# LTM8074.net
KiCad netlist of a schematic drawn in Altium Designer
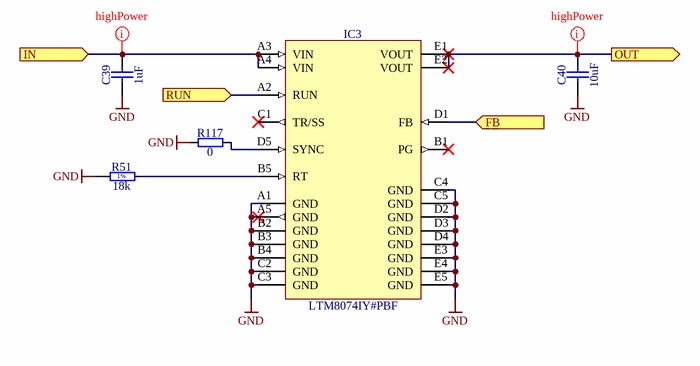
[diagram p0: LTM8074.SchDoc]

(export (version "E")
  (design (tool "Eeschema 10.0.6"))
  (components
    (comp (ref "C39")
      (value "1uF")
      (footprint "CAPC2012X110N")
      (description "Non-polarised capacitor")
      (fields
        (field (name "PART NUMBER") "CC0805_1UF_50V_10%_X7R")
        (field (name "VOLTAGE") "50V")
        (field (name "AUTHOR") "CERN DEM JLC")
      )
      (libsource (lib "Capacitors") (part "Capacitor - non polarized"))
    )
    (comp (ref "C40")
      (value "10uF")
      (footprint "CAPC2012X95N")
      (description "Non-polarised capacitor")
      (fields
        (field (name "PART NUMBER") "CC0805_10UF_25V_10%_X5R")
        (field (name "VOLTAGE") "25V")
        (field (name "AUTHOR") "CERN DEM JLC")
      )
      (libsource (lib "Capacitors") (part "Capacitor - non polarized"))
    )
    (comp (ref "IC3")
      (value "LTM8074IY#PBF")
      (footprint "BGA25C65P5X5_400X400X198")
      (description "40VIN, 1.2A Silent Switcher µModule Regulator")
      (fields (field (name "MANUFACTURER") "LINEAR TECHNOLOGY") (field (name "AUTHOR") "CERN DEM JLC"))
      (libsource (lib "ICs And Semiconductors") (part "LTM8074"))
    )
    (comp (ref "R51")
      (value "18k")
      (footprint "RESC1608X55N")
      (description "Resistor - 1%")
      (fields
        (field (name "PART NUMBER") "R0603_18K_1%_0.1W_100PPM")
        (field (name "POWER") "0.1W")
        (field (name "AUTHOR") "CERN DEM JLC")
      )
      (libsource (lib "Resistors") (part "Resistor - 1%"))
    )
    (comp (ref "R117")
      (value "0")
      (footprint "RESC1608X55N")
      (description "Resistor")
      (fields
        (field (name "PART NUMBER") "R0603_0R_JUMPER")
        (field (name "MANUFACTURER") "GENERIC")
        (field (name "AUTHOR") "CERN DEM JLC")
      )
      (libsource (lib "Resistors") (part "Resistor"))
    )
  )
  (nets
    (net (code "1") (name "/FB") (class "Default")
      (node (ref "IC3") (pin "D1") (pinfunction "FB_D1") (pintype "input"))
    )
    (net (code "2") (name "/IN") (class "Default")
      (node (ref "C39") (pin "2") (pinfunction "2_2") (pintype "passive"))
      (node (ref "IC3") (pin "A3") (pinfunction "VIN_A3") (pintype "input"))
      (node (ref "IC3") (pin "A4") (pinfunction "VIN_A4") (pintype "input"))
    )
    (net (code "3") (name "/OUT") (class "Default")
      (node (ref "C40") (pin "2") (pinfunction "2_2") (pintype "passive"))
      (node (ref "IC3") (pin "E1") (pinfunction "VOUT_E1") (pintype "power_in"))
      (node (ref "IC3") (pin "E2") (pinfunction "VOUT_E2") (pintype "power_in"))
    )
    (net (code "4") (name "/RUN") (class "Default")
      (node (ref "IC3") (pin "A2") (pinfunction "RUN_A2") (pintype "input"))
    )
    (net (code "5") (name "GND") (class "Default")
      (node (ref "C39") (pin "1") (pinfunction "1_1") (pintype "passive"))
      (node (ref "C40") (pin "1") (pinfunction "1_1") (pintype "passive"))
      (node (ref "IC3") (pin "A1") (pinfunction "GND_A1") (pintype "power_in"))
      (node (ref "IC3") (pin "A5") (pinfunction "GND_A5") (pintype "output"))
      (node (ref "IC3") (pin "B2") (pinfunction "GND_B2") (pintype "power_in"))
      (node (ref "IC3") (pin "B3") (pinfunction "GND_B3") (pintype "power_in"))
      (node (ref "IC3") (pin "B4") (pinfunction "GND_B4") (pintype "power_in"))
      (node (ref "IC3") (pin "C2") (pinfunction "GND_C2") (pintype "power_in"))
      (node (ref "IC3") (pin "C3") (pinfunction "GND_C3") (pintype "power_in"))
      (node (ref "IC3") (pin "C4") (pinfunction "GND_C4") (pintype "power_in"))
      (node (ref "IC3") (pin "C5") (pinfunction "GND_C5") (pintype "power_in"))
      (node (ref "IC3") (pin "D2") (pinfunction "GND_D2") (pintype "power_in"))
      (node (ref "IC3") (pin "D3") (pinfunction "GND_D3") (pintype "power_in"))
      (node (ref "IC3") (pin "D4") (pinfunction "GND_D4") (pintype "power_in"))
      (node (ref "IC3") (pin "E3") (pinfunction "GND_E3") (pintype "power_in"))
      (node (ref "IC3") (pin "E4") (pinfunction "GND_E4") (pintype "power_in"))
      (node (ref "IC3") (pin "E5") (pinfunction "GND_E5") (pintype "power_in"))
      (node (ref "R117") (pin "1") (pinfunction "1_1") (pintype "passive"))
      (node (ref "R51") (pin "1") (pinfunction "1_1") (pintype "passive"))
    )
    (net (code "6") (name "Net-(IC3-RT)") (class "Default")
      (node (ref "IC3") (pin "B5") (pinfunction "RT_B5") (pintype "input"))
      (node (ref "R51") (pin "2") (pinfunction "2_2") (pintype "passive"))
    )
    (net (code "7") (name "Net-(IC3-SYNC)") (class "Default")
      (node (ref "IC3") (pin "D5") (pinfunction "SYNC_D5") (pintype "input"))
      (node (ref "R117") (pin "2") (pinfunction "2_2") (pintype "passive"))
    )
    (net (code "8") (name "unconnected-(IC3-PG-PadB1)") (class "Default")
      (node (ref "IC3") (pin "B1") (pinfunction "PG_B1") (pintype "output+no_connect"))
    )
    (net (code "9") (name "unconnected-(IC3-TR{slash}SS-PadC1)") (class "Default")
      (node (ref "IC3") (pin "C1") (pinfunction "TR/SS_C1") (pintype "output+no_connect"))
    )
  )
)
